# Power.net
KiCad netlist of a schematic drawn in Altium Designer
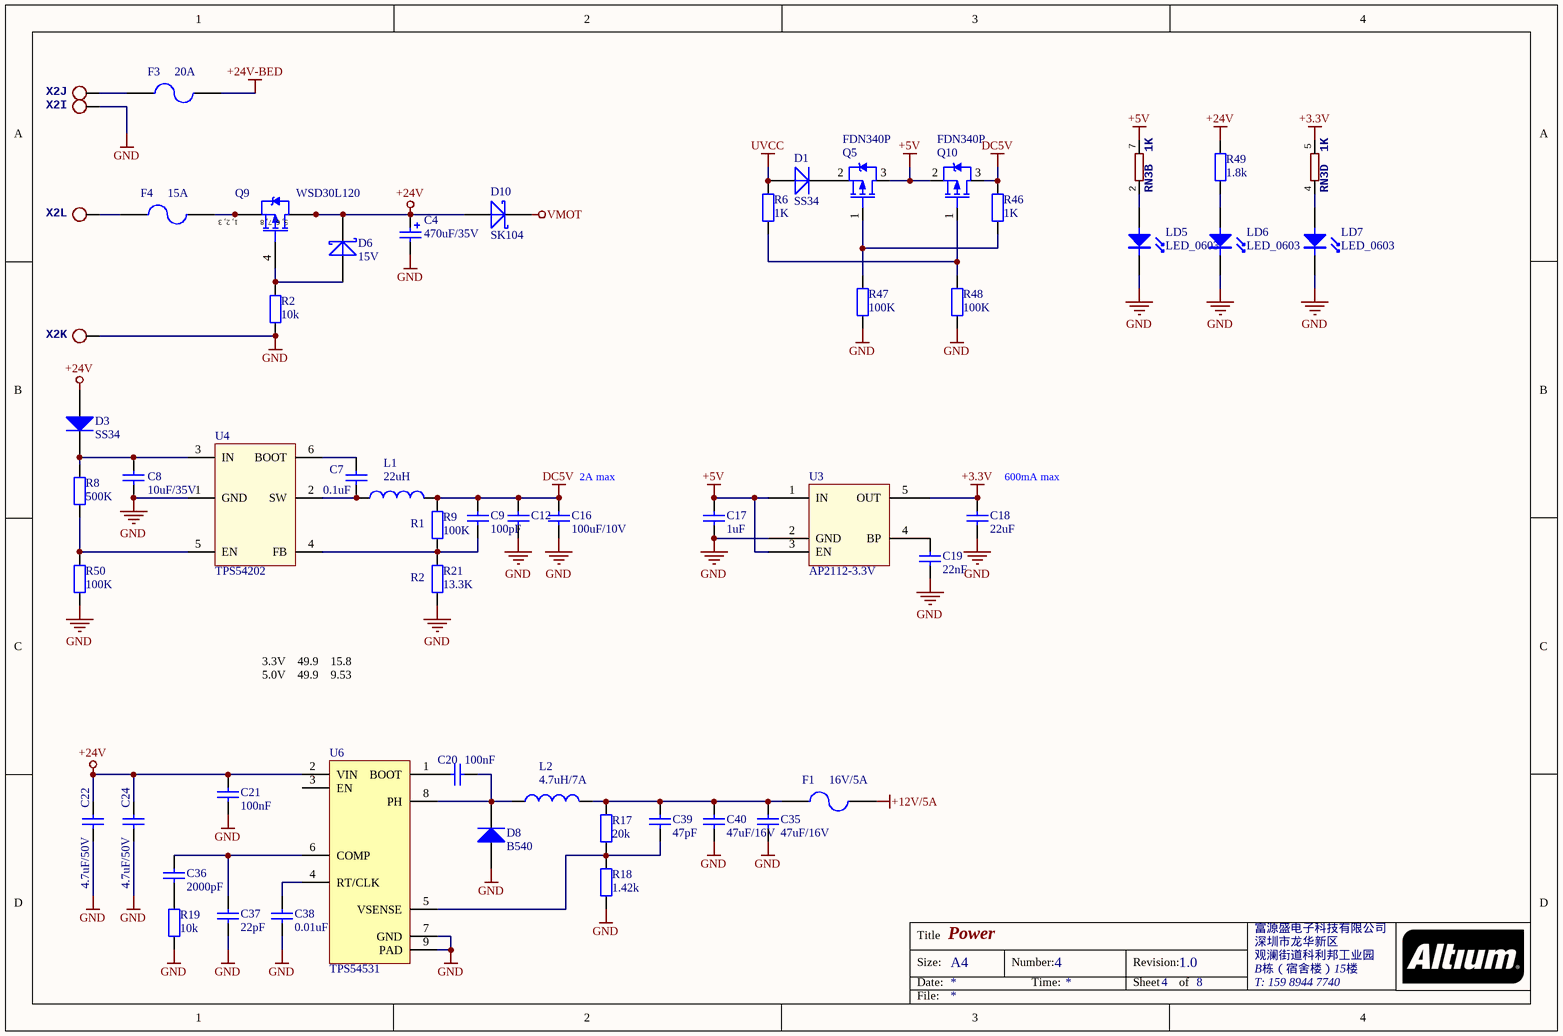
[diagram p0: Power.SchDoc]

(export (version "E")
  (design (tool "Eeschema 10.0.6"))
  (components
    (comp (ref "C4")
      (value "470uF/35V")
      (footprint "RCL_E5-10,5 - 1/2")
      (description "RO ELCO 100uF 20% 35V CASE-D EEEFP PAN")
      (libsource (lib "Ultimaker") (part "Capacitor Polarity"))
    )
    (comp (ref "C7")
      (value "0.1uF")
      (footprint "CAP0402")
      (description "RO C0G 22pF 2% 50V  0603")
      (libsource (lib "Ultimaker") (part "Capacitor"))
    )
    (comp (ref "C8") (value "10uF/35V") (footprint "CAP1206") (libsource (lib "接插件库") (part "Capacitor")))
    (comp (ref "C9")
      (value "100pF")
      (footprint "CAP0402")
      (description "RO C0G 22pF 2% 50V  0603")
      (libsource (lib "Ultimaker") (part "Capacitor"))
    )
    (comp (ref "C12")
      (value "100uF/10V")
      (footprint "CAP1206")
      (description "RO C0G 22pF 2% 50V  0603")
      (libsource (lib "Ultimaker") (part "Capacitor"))
    )
    (comp (ref "C16")
      (value "100uF/10V")
      (footprint "CAP1206")
      (description "RO C0G 22pF 2% 50V  0603")
      (libsource (lib "Ultimaker") (part "Capacitor"))
    )
    (comp (ref "C17")
      (value "1uF")
      (footprint "CAP0603")
      (description "RO C0G 22pF 2% 50V  0603")
      (libsource (lib "Ultimaker") (part "Capacitor"))
    )
    (comp (ref "C18")
      (value "22uF")
      (footprint "CAP0805")
      (description "RO C0G 22pF 2% 50V  0603")
      (libsource (lib "Ultimaker") (part "Capacitor"))
    )
    (comp (ref "C19")
      (value "22nF")
      (footprint "CAP0603")
      (description "RO C0G 22pF 2% 50V  0603")
      (libsource (lib "Ultimaker") (part "Capacitor"))
    )
    (comp (ref "C20")
      (value "100nF")
      (footprint "CAP0603")
      (description "RO C0G 22pF 2% 50V  0603")
      (libsource (lib "Ultimaker") (part "Capacitor"))
    )
    (comp (ref "C21")
      (value "100nF")
      (footprint "CAP0603")
      (description "RO C0G 22pF 2% 50V  0603")
      (libsource (lib "Ultimaker") (part "Capacitor"))
    )
    (comp (ref "C22")
      (value "4.7uF/50V")
      (footprint "CAP1206")
      (description "RO C0G 22pF 2% 50V  0603")
      (libsource (lib "Ultimaker") (part "Capacitor"))
    )
    (comp (ref "C24")
      (value "4.7uF/50V")
      (footprint "CAP1206")
      (description "RO C0G 22pF 2% 50V  0603")
      (libsource (lib "Ultimaker") (part "Capacitor"))
    )
    (comp (ref "C35")
      (value "47uF/16V")
      (footprint "CAP1206")
      (description "RO C0G 22pF 2% 50V  0603")
      (libsource (lib "Ultimaker") (part "Capacitor"))
    )
    (comp (ref "C36")
      (value "2000pF")
      (footprint "CAP0603")
      (description "RO C0G 22pF 2% 50V  0603")
      (libsource (lib "Ultimaker") (part "Capacitor"))
    )
    (comp (ref "C37")
      (value "22pF")
      (footprint "CAP0603")
      (description "RO C0G 22pF 2% 50V  0603")
      (libsource (lib "Ultimaker") (part "Capacitor"))
    )
    (comp (ref "C38")
      (value "0.01uF")
      (footprint "CAP0603")
      (description "RO C0G 22pF 2% 50V  0603")
      (libsource (lib "Ultimaker") (part "Capacitor"))
    )
    (comp (ref "C39")
      (value "47pF")
      (footprint "CAP0603")
      (description "RO C0G 22pF 2% 50V  0603")
      (libsource (lib "Ultimaker") (part "Capacitor"))
    )
    (comp (ref "C40")
      (value "47uF/16V")
      (footprint "CAP1206")
      (description "RO C0G 22pF 2% 50V  0603")
      (libsource (lib "Ultimaker") (part "Capacitor"))
    )
    (comp (ref "D1")
      (value "SS34")
      (footprint "SOD123")
      (description "RO DIODE S1G DO-214AC")
      (libsource (lib "Ultimaker2") (part "Diode_1"))
    )
    (comp (ref "D3")
      (value "SS34")
      (footprint "DO214AC (SMA)")
      (description "Default Diode")
      (fields (field (name "PUBLISHER") "Altium Limited"))
      (libsource (lib "Miscellaneous Devices") (part "Diode"))
    )
    (comp (ref "D6")
      (value "15V")
      (footprint "SOD123")
      (description "RO DIODE SSB44-E3/52T SMB VISHAY")
      (fields (field (name "MFG") "VISHAY"))
      (libsource (lib "Ultimaker2") (part "Schottky"))
    )
    (comp (ref "D8")
      (value "B540")
      (footprint "SMC/DO-214AB")
      (description "Default Diode")
      (fields (field (name "PUBLISHER") "Altium Limited"))
      (libsource (lib "Miscellaneous Devices") (part "Diode"))
    )
    (comp (ref "D10")
      (value "SK104")
      (footprint "POWEREDI5")
      (description "RO DIODE SSB44-E3/52T SMB VISHAY")
      (fields (field (name "MFG") "VISHAY"))
      (libsource (lib "Ultimaker2") (part "Schottky"))
    )
    (comp (ref "F1")
      (value "16V/5A")
      (footprint "RES1206")
      (description "Fuse")
      (fields (field (name "PUBLISHER") "Altium Limited"))
      (libsource (lib "Miscellaneous Devices") (part "Fuse 2"))
    )
    (comp (ref "F3")
      (value "20A")
      (footprint "Fuse_Holder_TH_3568")
      (description "Fuse")
      (fields (field (name "PUBLISHER") "Altium Limited"))
      (libsource (lib "Miscellaneous Devices") (part "Fuse 2"))
    )
    (comp (ref "F4")
      (value "15A")
      (footprint "Fuse_Holder_TH_3568")
      (description "Fuse")
      (fields (field (name "PUBLISHER") "Altium Limited"))
      (libsource (lib "Miscellaneous Devices") (part "Fuse 2"))
    )
    (comp (ref "L1")
      (value "22uH")
      (footprint "NRS6045")
      (description "Inductor")
      (fields (field (name "PUBLISHER") "Altium Limited"))
      (libsource (lib "Miscellaneous Devices") (part "Inductor"))
    )
    (comp (ref "L2")
      (value "4.7uH/7A")
      (footprint "10X10屏蔽电感 5A")
      (description "Inductor")
      (fields (field (name "PUBLISHER") "Altium Limited"))
      (libsource (lib "Miscellaneous Devices") (part "Inductor"))
    )
    (comp (ref "LD5") (value "LED_0603") (footprint "LED0603") (libsource (lib "接插件库") (part "LED_0603")))
    (comp (ref "LD6") (value "LED_0603") (footprint "LED0603") (libsource (lib "接插件库") (part "LED_0603")))
    (comp (ref "LD7") (value "LED_0603") (footprint "LED0603") (libsource (lib "接插件库") (part "LED_0603")))
    (comp (ref "Q5") (value "FDN340P") (footprint "SOT23-3") (libsource (lib "接插件库") (part "FDN340P")))
    (comp (ref "Q9")
      (value "WSD30L120")
      (footprint "AO_DFN5x6")
      (description "PFET Power SO8")
      (fields (field (name "PART NUMBER") "SI7157DP") (field (name "MANUFACTURER") "Vishay"))
      (libsource (lib "Semiconductors_Transistors") (part "P-MOSFET Power SO8"))
    )
    (comp (ref "Q10") (value "FDN340P") (footprint "SOT23-3") (libsource (lib "接插件库") (part "FDN340P")))
    (comp (ref "R2")
      (value "10k")
      (footprint "RES0603")
      (description "RO RES 10k0 1% 0,063W  0603")
      (libsource (lib "Ultimaker") (part "Resistor"))
    )
    (comp (ref "R6")
      (value "1K")
      (footprint "RES0402")
      (description "RO RES 22E0 1% 0,063W 0603")
      (libsource (lib "") (part "Resistor_1"))
    )
    (comp (ref "R8") (value "500K") (footprint "RES0402") (libsource (lib "接插件库") (part "Resistor")))
    (comp (ref "R9")
      (value "100K")
      (footprint "RES0402")
      (description "RO RES 10k0 1% 0,063W  0603")
      (libsource (lib "Ultimaker") (part "Resistor"))
    )
    (comp (ref "R17")
      (value "20k")
      (footprint "RES0603")
      (description "RO RES 10k0 1% 0,063W  0603")
      (libsource (lib "Ultimaker") (part "Resistor"))
    )
    (comp (ref "R18")
      (value "1.42k")
      (footprint "RES0603")
      (description "RO RES 10k0 1% 0,063W  0603")
      (libsource (lib "Ultimaker") (part "Resistor"))
    )
    (comp (ref "R19")
      (value "10k")
      (footprint "RES0603")
      (description "RO RES 10k0 1% 0,063W  0603")
      (libsource (lib "Ultimaker") (part "Resistor"))
    )
    (comp (ref "R21")
      (value "13.3K")
      (footprint "RES0402")
      (description "RO RES 10k0 1% 0,063W  0603")
      (libsource (lib "Ultimaker") (part "Resistor"))
    )
    (comp (ref "R46")
      (value "1K")
      (footprint "RES0402")
      (description "RO RES 22E0 1% 0,063W 0603")
      (libsource (lib "") (part "Resistor_1"))
    )
    (comp (ref "R47")
      (value "100K")
      (footprint "RES0402")
      (description "RO RES 22E0 1% 0,063W 0603")
      (libsource (lib "") (part "Resistor_1"))
    )
    (comp (ref "R48")
      (value "100K")
      (footprint "RES0402")
      (description "RO RES 22E0 1% 0,063W 0603")
      (libsource (lib "") (part "Resistor_1"))
    )
    (comp (ref "R49")
      (value "1.8k")
      (footprint "RES0402")
      (description "RO RES 1k0 1% 0,1W  0603")
      (libsource (lib "") (part "Resistor_1"))
    )
    (comp (ref "R50") (value "100K") (footprint "RES0402") (libsource (lib "接插件库") (part "Resistor")))
    (comp (ref "RN3")
      (value "1K")
      (footprint "RESISTOR-DIL_CAY16")
      (libsource (lib "接插件库") (part "RESISTOR-DIL_4R-NCAT16"))
    )
    (comp (ref "U3")
      (value "AP2112-3.3V")
      (footprint "SOT23-5")
      (libsource (lib "接插件库") (part "RT9193-XXXX"))
    )
    (comp (ref "U4") (value "TPS54202") (footprint "SOT23-6N") (libsource (lib "接插件库") (part "TPS54202")))
    (comp (ref "U6") (value "TPS54531") (footprint "SO8_WITH PAD") (libsource (lib "接插件库") (part "TPS54531")))
    (comp (ref "X2")
      (value "5.08-12P")
      (footprint "CON-PHOENIX-508_MKDSN1,5/12-5,08")
      (fields (field (name "MPN") "SMKDSN1,5/10-5,08"))
      (libsource (lib "接插件库") (part "CON-PHOENIX-508_MKDSN1,5/12-5,08"))
    )
  )
  (nets
    (net (code "1") (name "+3.3V") (class "Default")
      (node (ref "C18") (pin "2") (pinfunction "2_2") (pintype "passive"))
      (node (ref "RN3") (pin "5") (pinfunction "2_5") (pintype "passive"))
      (node (ref "U3") (pin "5") (pinfunction "OUT_5") (pintype "passive"))
    )
    (net (code "2") (name "+5V") (class "Default")
      (node (ref "C17") (pin "2") (pinfunction "2_2") (pintype "passive"))
      (node (ref "Q10") (pin "2") (pinfunction "S_2") (pintype "passive"))
      (node (ref "Q5") (pin "3") (pinfunction "D_3") (pintype "passive"))
      (node (ref "RN3") (pin "7") (pinfunction "2_7") (pintype "passive"))
      (node (ref "U3") (pin "1") (pinfunction "IN_1") (pintype "passive"))
      (node (ref "U3") (pin "3") (pinfunction "EN_3") (pintype "passive"))
    )
    (net (code "3") (name "+12V{slash}5A") (class "Default")
      (node (ref "F1") (pin "2") (pinfunction "2_2") (pintype "passive"))
    )
    (net (code "4") (name "+24V") (class "Default")
      (node (ref "C21") (pin "2") (pinfunction "2_2") (pintype "passive"))
      (node (ref "C22") (pin "1") (pinfunction "1_1") (pintype "passive"))
      (node (ref "C24") (pin "1") (pinfunction "1_1") (pintype "passive"))
      (node (ref "C4") (pin "1") (pinfunction "1_1") (pintype "passive"))
      (node (ref "D10") (pin "1") (pinfunction "A_1") (pintype "passive"))
      (node (ref "D3") (pin "1") (pinfunction "A_1") (pintype "passive"))
      (node (ref "D6") (pin "2") (pinfunction "K_2") (pintype "passive"))
      (node (ref "Q9") (pin "5") (pinfunction "D_5") (pintype "passive"))
      (node (ref "Q9") (pin "6") (pinfunction "D_6") (pintype "passive"))
      (node (ref "Q9") (pin "7") (pinfunction "D_7") (pintype "passive"))
      (node (ref "Q9") (pin "8") (pinfunction "D_8") (pintype "passive"))
      (node (ref "R49") (pin "2") (pinfunction "2_2") (pintype "passive"))
      (node (ref "U6") (pin "2") (pinfunction "VIN_2") (pintype "passive"))
    )
    (net (code "5") (name "+24V-BED") (class "Default")
      (node (ref "F3") (pin "2") (pinfunction "2_2") (pintype "passive"))
    )
    (net (code "6") (name "DC5V") (class "Default")
      (node (ref "C12") (pin "1") (pinfunction "1_1") (pintype "passive"))
      (node (ref "C16") (pin "1") (pinfunction "1_1") (pintype "passive"))
      (node (ref "C9") (pin "1") (pinfunction "1_1") (pintype "passive"))
      (node (ref "L1") (pin "2") (pinfunction "2_2") (pintype "passive"))
      (node (ref "Q10") (pin "3") (pinfunction "D_3") (pintype "passive"))
      (node (ref "R46") (pin "2") (pinfunction "2_2") (pintype "passive"))
      (node (ref "R9") (pin "1") (pinfunction "1_1") (pintype "passive"))
    )
    (net (code "7") (name "GND") (class "Default")
      (node (ref "C12") (pin "2") (pinfunction "2_2") (pintype "passive"))
      (node (ref "C16") (pin "2") (pinfunction "2_2") (pintype "passive"))
      (node (ref "C17") (pin "1") (pinfunction "1_1") (pintype "passive"))
      (node (ref "C18") (pin "1") (pinfunction "1_1") (pintype "passive"))
      (node (ref "C19") (pin "1") (pinfunction "1_1") (pintype "passive"))
      (node (ref "C21") (pin "1") (pinfunction "1_1") (pintype "passive"))
      (node (ref "C22") (pin "2") (pinfunction "2_2") (pintype "passive"))
      (node (ref "C24") (pin "2") (pinfunction "2_2") (pintype "passive"))
      (node (ref "C35") (pin "2") (pinfunction "2_2") (pintype "passive"))
      (node (ref "C37") (pin "1") (pinfunction "1_1") (pintype "passive"))
      (node (ref "C38") (pin "1") (pinfunction "1_1") (pintype "passive"))
      (node (ref "C4") (pin "2") (pinfunction "2_2") (pintype "passive"))
      (node (ref "C40") (pin "2") (pinfunction "2_2") (pintype "passive"))
      (node (ref "C8") (pin "1") (pinfunction "1_1") (pintype "passive"))
      (node (ref "D8") (pin "1") (pinfunction "A_1") (pintype "passive"))
      (node (ref "LD5") (pin "1") (pinfunction "A_1") (pintype "passive"))
      (node (ref "LD6") (pin "1") (pinfunction "A_1") (pintype "passive"))
      (node (ref "LD7") (pin "1") (pinfunction "A_1") (pintype "passive"))
      (node (ref "R18") (pin "2") (pinfunction "2_2") (pintype "passive"))
      (node (ref "R19") (pin "2") (pinfunction "2_2") (pintype "passive"))
      (node (ref "R2") (pin "2") (pinfunction "2_2") (pintype "passive"))
      (node (ref "R21") (pin "2") (pinfunction "2_2") (pintype "passive"))
      (node (ref "R47") (pin "1") (pinfunction "1_1") (pintype "passive"))
      (node (ref "R48") (pin "1") (pinfunction "1_1") (pintype "passive"))
      (node (ref "R50") (pin "1") (pinfunction "1_1") (pintype "passive"))
      (node (ref "U3") (pin "2") (pinfunction "GND_2") (pintype "passive"))
      (node (ref "U4") (pin "1") (pinfunction "GND_1") (pintype "passive"))
      (node (ref "U6") (pin "7") (pinfunction "GND_7") (pintype "passive"))
      (node (ref "U6") (pin "9") (pinfunction "PAD_9") (pintype "passive"))
      (node (ref "X2") (pin "11") (pinfunction "KL_11") (pintype "passive"))
      (node (ref "X2") (pin "9") (pinfunction "KL_9") (pintype "passive"))
    )
    (net (code "8") (name "Net-(C35-Pad1)") (class "Default")
      (node (ref "C35") (pin "1") (pinfunction "1_1") (pintype "passive"))
      (node (ref "C39") (pin "1") (pinfunction "1_1") (pintype "passive"))
      (node (ref "C40") (pin "1") (pinfunction "1_1") (pintype "passive"))
      (node (ref "F1") (pin "1") (pinfunction "1_1") (pintype "passive"))
      (node (ref "L2") (pin "2") (pinfunction "2_2") (pintype "passive"))
      (node (ref "R17") (pin "1") (pinfunction "1_1") (pintype "passive"))
    )
    (net (code "9") (name "Net-(C36-Pad1)") (class "Default")
      (node (ref "C36") (pin "1") (pinfunction "1_1") (pintype "passive"))
      (node (ref "R19") (pin "1") (pinfunction "1_1") (pintype "passive"))
    )
    (net (code "10") (name "Net-(D1-K)") (class "Default")
      (node (ref "D1") (pin "2") (pinfunction "K_2") (pintype "passive"))
      (node (ref "Q5") (pin "2") (pinfunction "S_2") (pintype "passive"))
    )
    (net (code "11") (name "Net-(D3-K)") (class "Default")
      (node (ref "C8") (pin "2") (pinfunction "2_2") (pintype "passive"))
      (node (ref "D3") (pin "2") (pinfunction "K_2") (pintype "passive"))
      (node (ref "R8") (pin "2") (pinfunction "2_2") (pintype "passive"))
      (node (ref "U4") (pin "3") (pinfunction "IN_3") (pintype "passive"))
    )
    (net (code "12") (name "Net-(D6-A)") (class "Default")
      (node (ref "D6") (pin "1") (pinfunction "A_1") (pintype "passive"))
      (node (ref "Q9") (pin "4") (pinfunction "G_4") (pintype "passive"))
      (node (ref "R2") (pin "1") (pinfunction "1_1") (pintype "passive"))
    )
    (net (code "13") (name "Net-(D8-K)") (class "Default")
      (node (ref "C20") (pin "1") (pinfunction "1_1") (pintype "passive"))
      (node (ref "D8") (pin "2") (pinfunction "K_2") (pintype "passive"))
      (node (ref "L2") (pin "1") (pinfunction "1_1") (pintype "passive"))
      (node (ref "U6") (pin "8") (pinfunction "PH_8") (pintype "passive"))
    )
    (net (code "14") (name "Net-(F4-Pad2)") (class "Default")
      (node (ref "F4") (pin "2") (pinfunction "2_2") (pintype "passive"))
      (node (ref "Q9") (pin "1") (pinfunction "S_1") (pintype "passive"))
      (node (ref "Q9") (pin "2") (pinfunction "S_2") (pintype "passive"))
      (node (ref "Q9") (pin "3") (pinfunction "S_3") (pintype "passive"))
    )
    (net (code "15") (name "Net-(LD5-K)") (class "Default")
      (node (ref "LD5") (pin "2") (pinfunction "K_2") (pintype "passive"))
      (node (ref "RN3") (pin "2") (pinfunction "1_2") (pintype "passive"))
    )
    (net (code "16") (name "Net-(LD6-K)") (class "Default")
      (node (ref "LD6") (pin "2") (pinfunction "K_2") (pintype "passive"))
      (node (ref "R49") (pin "1") (pinfunction "1_1") (pintype "passive"))
    )
    (net (code "17") (name "Net-(LD7-K)") (class "Default")
      (node (ref "LD7") (pin "2") (pinfunction "K_2") (pintype "passive"))
      (node (ref "RN3") (pin "4") (pinfunction "1_4") (pintype "passive"))
    )
    (net (code "18") (name "Net-(Q5-G)") (class "Default")
      (node (ref "Q5") (pin "1") (pinfunction "G_1") (pintype "passive"))
      (node (ref "R46") (pin "1") (pinfunction "1_1") (pintype "passive"))
      (node (ref "R47") (pin "2") (pinfunction "2_2") (pintype "passive"))
    )
    (net (code "19") (name "Net-(Q10-G)") (class "Default")
      (node (ref "Q10") (pin "1") (pinfunction "G_1") (pintype "passive"))
      (node (ref "R48") (pin "2") (pinfunction "2_2") (pintype "passive"))
      (node (ref "R6") (pin "1") (pinfunction "1_1") (pintype "passive"))
    )
    (net (code "20") (name "Net-(U3-BP)") (class "Default")
      (node (ref "C19") (pin "2") (pinfunction "2_2") (pintype "passive"))
      (node (ref "U3") (pin "4") (pinfunction "BP_4") (pintype "passive"))
    )
    (net (code "21") (name "Net-(U4-BOOT)") (class "Default")
      (node (ref "C7") (pin "1") (pinfunction "1_1") (pintype "passive"))
      (node (ref "U4") (pin "6") (pinfunction "BOOT_6") (pintype "passive"))
    )
    (net (code "22") (name "Net-(U4-EN)") (class "Default")
      (node (ref "R50") (pin "2") (pinfunction "2_2") (pintype "passive"))
      (node (ref "R8") (pin "1") (pinfunction "1_1") (pintype "passive"))
      (node (ref "U4") (pin "5") (pinfunction "EN_5") (pintype "passive"))
    )
    (net (code "23") (name "Net-(U4-FB)") (class "Default")
      (node (ref "C9") (pin "2") (pinfunction "2_2") (pintype "passive"))
      (node (ref "R21") (pin "1") (pinfunction "1_1") (pintype "passive"))
      (node (ref "R9") (pin "2") (pinfunction "2_2") (pintype "passive"))
      (node (ref "U4") (pin "4") (pinfunction "FB_4") (pintype "passive"))
    )
    (net (code "24") (name "Net-(U4-SW)") (class "Default")
      (node (ref "C7") (pin "2") (pinfunction "2_2") (pintype "passive"))
      (node (ref "L1") (pin "1") (pinfunction "1_1") (pintype "passive"))
      (node (ref "U4") (pin "2") (pinfunction "SW_2") (pintype "passive"))
    )
    (net (code "25") (name "Net-(U6-BOOT)") (class "Default")
      (node (ref "C20") (pin "2") (pinfunction "2_2") (pintype "passive"))
      (node (ref "U6") (pin "1") (pinfunction "BOOT_1") (pintype "passive"))
    )
    (net (code "26") (name "Net-(U6-COMP)") (class "Default")
      (node (ref "C36") (pin "2") (pinfunction "2_2") (pintype "passive"))
      (node (ref "C37") (pin "2") (pinfunction "2_2") (pintype "passive"))
      (node (ref "U6") (pin "6") (pinfunction "COMP_6") (pintype "passive"))
    )
    (net (code "27") (name "Net-(U6-RT{slash}CLK)") (class "Default")
      (node (ref "C38") (pin "2") (pinfunction "2_2") (pintype "passive"))
      (node (ref "U6") (pin "4") (pinfunction "RT/CLK_4") (pintype "passive"))
    )
    (net (code "28") (name "Net-(U6-VSENSE)") (class "Default")
      (node (ref "C39") (pin "2") (pinfunction "2_2") (pintype "passive"))
      (node (ref "R17") (pin "2") (pinfunction "2_2") (pintype "passive"))
      (node (ref "R18") (pin "1") (pinfunction "1_1") (pintype "passive"))
      (node (ref "U6") (pin "5") (pinfunction "VSENSE_5") (pintype "passive"))
    )
    (net (code "29") (name "Net-(X2J-KL)") (class "Default")
      (node (ref "F3") (pin "1") (pinfunction "1_1") (pintype "passive"))
      (node (ref "X2") (pin "10") (pinfunction "KL_10") (pintype "passive"))
    )
    (net (code "30") (name "Net-(X2L-KL)") (class "Default")
      (node (ref "F4") (pin "1") (pinfunction "1_1") (pintype "passive"))
      (node (ref "X2") (pin "12") (pinfunction "KL_12") (pintype "passive"))
    )
    (net (code "31") (name "UVCC") (class "Default")
      (node (ref "D1") (pin "1") (pinfunction "A_1") (pintype "passive"))
      (node (ref "R6") (pin "2") (pinfunction "2_2") (pintype "passive"))
    )
    (net (code "32") (name "VMOT") (class "Default")
      (node (ref "D10") (pin "2") (pinfunction "K_2") (pintype "passive"))
    )
    (net (code "33") (name "unconnected-(U6-EN-Pad3)") (class "Default")
      (node (ref "U6") (pin "3") (pinfunction "EN_3") (pintype "passive"))
    )
  )
)
